# bms_board.net
KiCad netlist of a schematic drawn in EAGLE
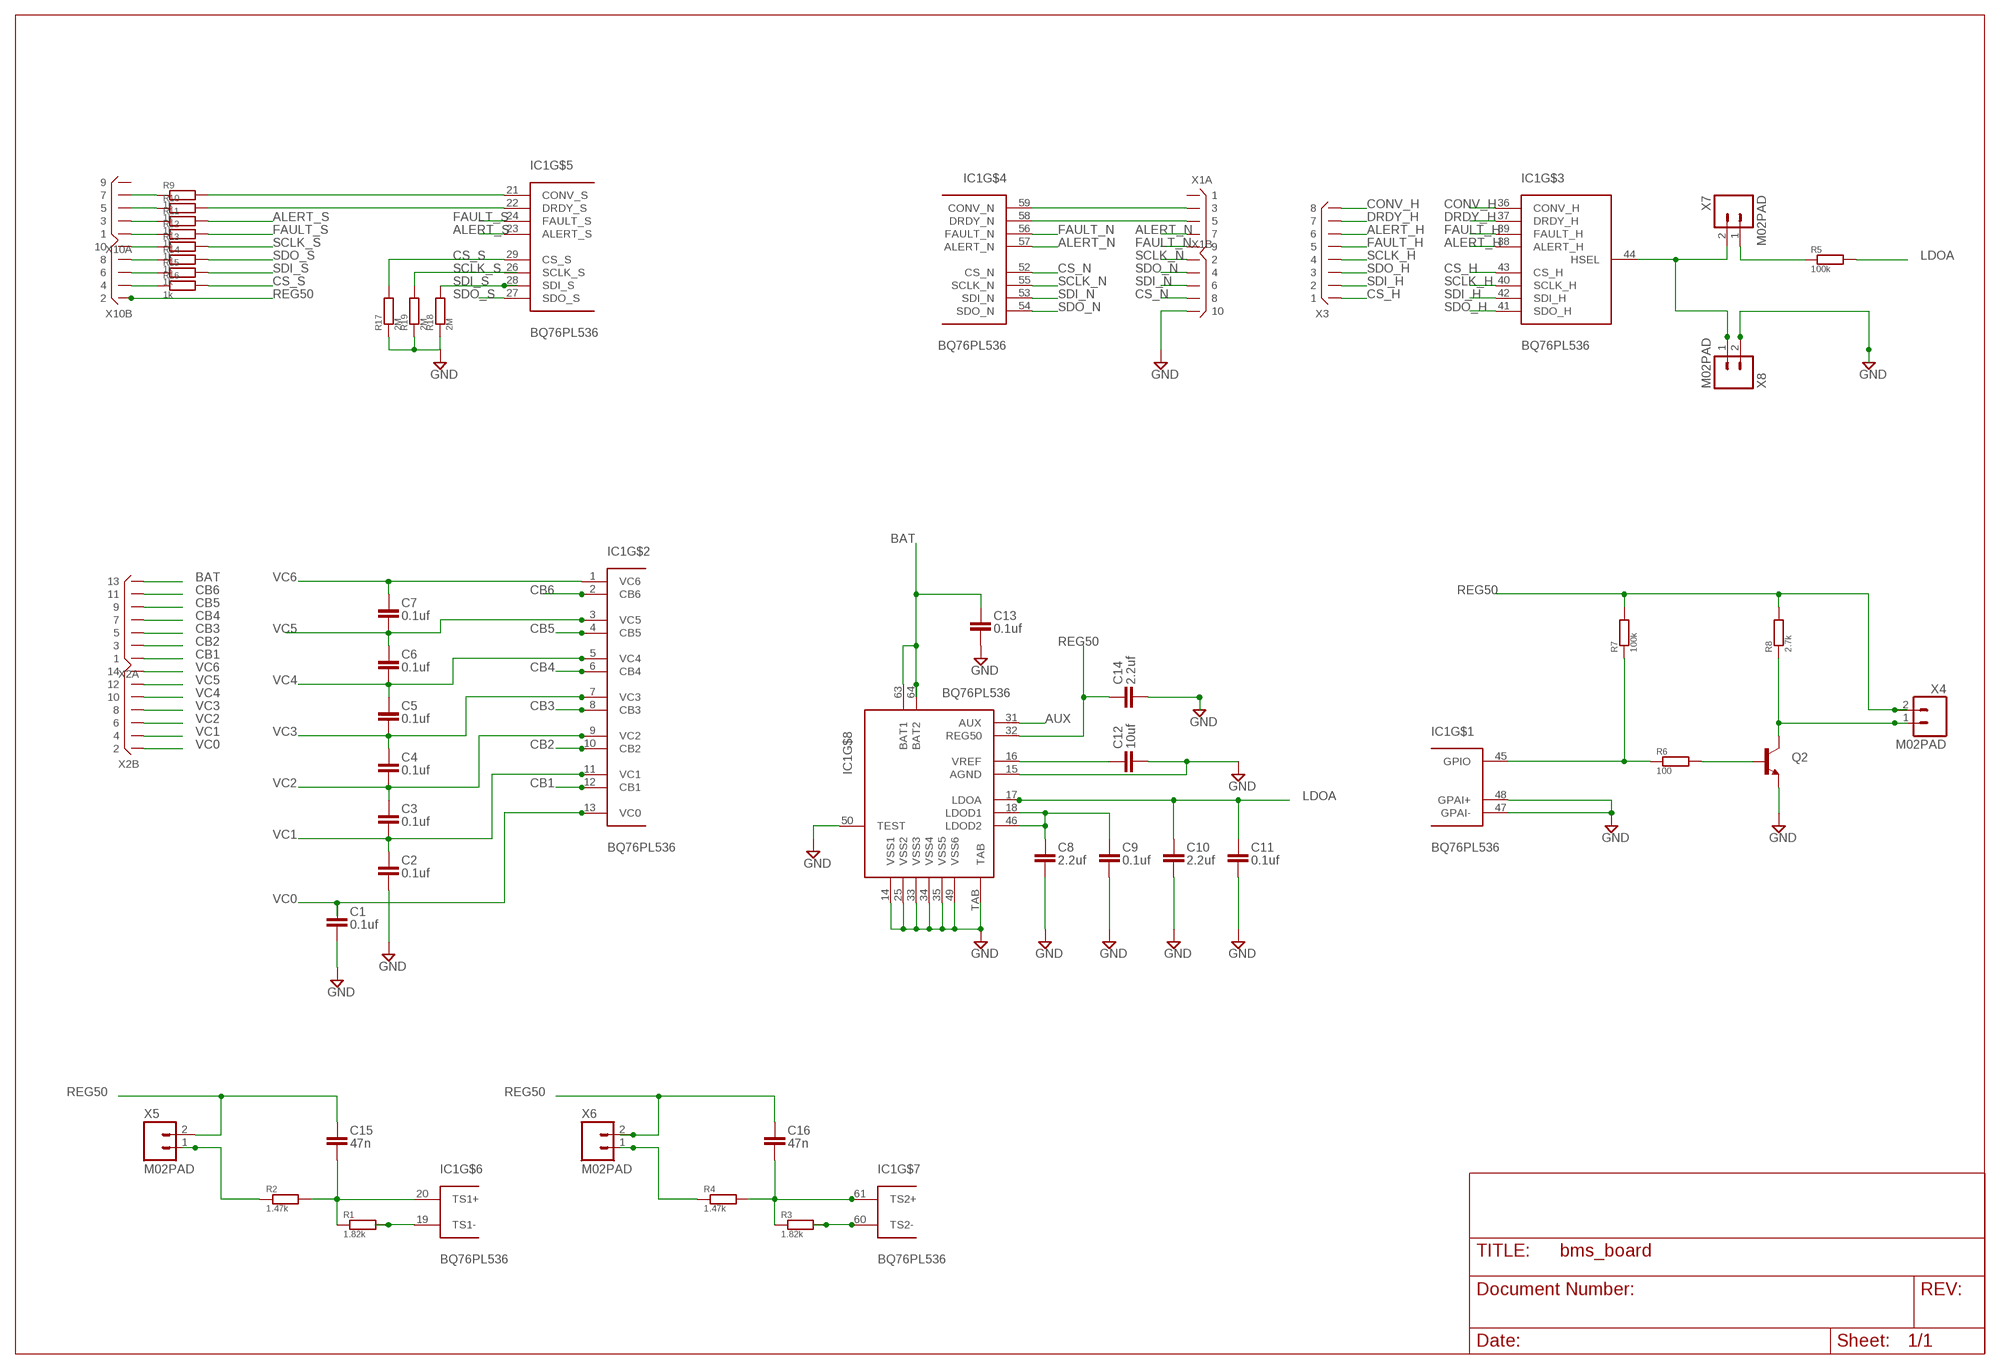
[diagram p0: schematic, sheet 1]

(export (version "E")
  (design (tool "Eeschema 10.0.6"))
  (components
    (comp (ref "C1")
      (value "0.1uf")
      (footprint "eagle-import:C0805")
      (libsource (lib "eagle-import") (part "CSTD"))
    )
    (comp (ref "C2")
      (value "0.1uf")
      (footprint "eagle-import:C0805")
      (libsource (lib "eagle-import") (part "CSTD"))
    )
    (comp (ref "C3")
      (value "0.1uf")
      (footprint "eagle-import:C0805")
      (libsource (lib "eagle-import") (part "CSTD"))
    )
    (comp (ref "C4")
      (value "0.1uf")
      (footprint "eagle-import:C0805")
      (libsource (lib "eagle-import") (part "CSTD"))
    )
    (comp (ref "C5")
      (value "0.1uf")
      (footprint "eagle-import:C0805")
      (libsource (lib "eagle-import") (part "CSTD"))
    )
    (comp (ref "C6")
      (value "0.1uf")
      (footprint "eagle-import:C0805")
      (libsource (lib "eagle-import") (part "CSTD"))
    )
    (comp (ref "C7")
      (value "0.1uf")
      (footprint "eagle-import:C0805")
      (libsource (lib "eagle-import") (part "CSTD"))
    )
    (comp (ref "C8")
      (value "2.2uf")
      (footprint "eagle-import:C0805")
      (libsource (lib "eagle-import") (part "CSTD"))
    )
    (comp (ref "C9")
      (value "0.1uf")
      (footprint "eagle-import:C0805")
      (libsource (lib "eagle-import") (part "CSTD"))
    )
    (comp (ref "C10")
      (value "2.2uf")
      (footprint "eagle-import:C0805")
      (libsource (lib "eagle-import") (part "CSTD"))
    )
    (comp (ref "C11")
      (value "0.1uf")
      (footprint "eagle-import:C0805")
      (libsource (lib "eagle-import") (part "CSTD"))
    )
    (comp (ref "C12")
      (value "10uf")
      (footprint "eagle-import:C0805")
      (libsource (lib "eagle-import") (part "CSTD"))
    )
    (comp (ref "C13")
      (value "0.1uf")
      (footprint "eagle-import:C0805")
      (libsource (lib "eagle-import") (part "CSTD"))
    )
    (comp (ref "C14")
      (value "2.2uf")
      (footprint "eagle-import:C0805")
      (libsource (lib "eagle-import") (part "CSTD"))
    )
    (comp (ref "C15")
      (value "47n")
      (footprint "eagle-import:C0805")
      (libsource (lib "eagle-import") (part "CSTD"))
    )
    (comp (ref "C16")
      (value "47n")
      (footprint "eagle-import:C0805")
      (libsource (lib "eagle-import") (part "CSTD"))
    )
    (comp (ref "IC1")
      (value "BQ76PL536")
      (footprint "eagle-import:LQFP-64")
      (libsource (lib "eagle-import") (part "BQ76PL536"))
    )
    (comp (ref "Q2")
      (value "TRANSISTOR_NPNSOT23")
      (footprint "eagle-import:SOT23")
      (libsource (lib "eagle-import") (part "TRANSISTOR_NPNSOT23"))
    )
    (comp (ref "R1")
      (value "1.82k")
      (footprint "eagle-import:R0805")
      (libsource (lib "eagle-import") (part "R"))
    )
    (comp (ref "R2")
      (value "1.47k")
      (footprint "eagle-import:R0805")
      (libsource (lib "eagle-import") (part "R"))
    )
    (comp (ref "R3")
      (value "1.82k")
      (footprint "eagle-import:R0805")
      (libsource (lib "eagle-import") (part "R"))
    )
    (comp (ref "R4")
      (value "1.47k")
      (footprint "eagle-import:R0805")
      (libsource (lib "eagle-import") (part "R"))
    )
    (comp (ref "R5")
      (value "100k")
      (footprint "eagle-import:R0805")
      (libsource (lib "eagle-import") (part "R"))
    )
    (comp (ref "R6")
      (value "100")
      (footprint "eagle-import:R0805")
      (libsource (lib "eagle-import") (part "R"))
    )
    (comp (ref "R7")
      (value "100k")
      (footprint "eagle-import:R0805")
      (libsource (lib "eagle-import") (part "R"))
    )
    (comp (ref "R8")
      (value "2.7k")
      (footprint "eagle-import:R0805")
      (libsource (lib "eagle-import") (part "R"))
    )
    (comp (ref "R9")
      (value "1k")
      (footprint "eagle-import:R0805")
      (libsource (lib "eagle-import") (part "R"))
    )
    (comp (ref "R10")
      (value "1k")
      (footprint "eagle-import:R0805")
      (libsource (lib "eagle-import") (part "R"))
    )
    (comp (ref "R11")
      (value "1k")
      (footprint "eagle-import:R0805")
      (libsource (lib "eagle-import") (part "R"))
    )
    (comp (ref "R12")
      (value "1k")
      (footprint "eagle-import:R0805")
      (libsource (lib "eagle-import") (part "R"))
    )
    (comp (ref "R13")
      (value "1k")
      (footprint "eagle-import:R0805")
      (libsource (lib "eagle-import") (part "R"))
    )
    (comp (ref "R14")
      (value "1k")
      (footprint "eagle-import:R0805")
      (libsource (lib "eagle-import") (part "R"))
    )
    (comp (ref "R15")
      (value "1k")
      (footprint "eagle-import:R0805")
      (libsource (lib "eagle-import") (part "R"))
    )
    (comp (ref "R16")
      (value "1k")
      (footprint "eagle-import:R0805")
      (libsource (lib "eagle-import") (part "R"))
    )
    (comp (ref "R17")
      (value "2M")
      (footprint "eagle-import:R0805")
      (libsource (lib "eagle-import") (part "R"))
    )
    (comp (ref "R18")
      (value "2M")
      (footprint "eagle-import:R0805")
      (libsource (lib "eagle-import") (part "R"))
    )
    (comp (ref "R19")
      (value "2M")
      (footprint "eagle-import:R0805")
      (libsource (lib "eagle-import") (part "R"))
    )
    (comp (ref "X1")
      (value "X05X2ICR")
      (footprint "eagle-import:X10ICR")
      (libsource (lib "eagle-import") (part "X05X2ICR"))
    )
    (comp (ref "X2")
      (value "X07X2IR")
      (footprint "eagle-import:X14R-IDC")
      (libsource (lib "eagle-import") (part "X07X2IR"))
    )
    (comp (ref "X3")
      (value "X08R")
      (footprint "eagle-import:X08R-SIL")
      (libsource (lib "eagle-import") (part "X08R"))
    )
    (comp (ref "X4")
      (value "M02PAD")
      (footprint "eagle-import:1X02")
      (libsource (lib "eagle-import") (part "M02PAD"))
    )
    (comp (ref "X5")
      (value "M02PAD")
      (footprint "eagle-import:1X02")
      (libsource (lib "eagle-import") (part "M02PAD"))
    )
    (comp (ref "X6")
      (value "M02PAD")
      (footprint "eagle-import:1X02")
      (libsource (lib "eagle-import") (part "M02PAD"))
    )
    (comp (ref "X7")
      (value "M02PAD")
      (footprint "eagle-import:1X02")
      (libsource (lib "eagle-import") (part "M02PAD"))
    )
    (comp (ref "X8")
      (value "M02PAD")
      (footprint "eagle-import:1X02")
      (libsource (lib "eagle-import") (part "M02PAD"))
    )
    (comp (ref "X10")
      (value "X05X2ICR")
      (footprint "eagle-import:X10ICR")
      (libsource (lib "eagle-import") (part "X05X2ICR"))
    )
  )
  (nets
    (net (code "1") (name "/ALERT_H") (class "Default")
      (node (ref "IC1") (pin "38") (pinfunction "ALERT_H_38") (pintype "bidirectional"))
      (node (ref "X3") (pin "6") (pinfunction "6_6") (pintype "bidirectional"))
    )
    (net (code "2") (name "/ALERT_N") (class "Default")
      (node (ref "IC1") (pin "57") (pinfunction "ALERT_N_57") (pintype "bidirectional"))
      (node (ref "X1") (pin "7") (pinfunction "7_7") (pintype "bidirectional"))
    )
    (net (code "3") (name "/ALERT_S") (class "Default")
      (node (ref "IC1") (pin "23") (pinfunction "ALERT_S_23") (pintype "bidirectional"))
      (node (ref "R11") (pin "2") (pinfunction "2_2") (pintype "passive"))
    )
    (net (code "4") (name "/AUX") (class "Default")
      (node (ref "IC1") (pin "31") (pinfunction "AUX_31") (pintype "bidirectional"))
    )
    (net (code "5") (name "/BAT") (class "Default")
      (node (ref "C13") (pin "2") (pinfunction "2_2") (pintype "passive"))
      (node (ref "IC1") (pin "63") (pinfunction "BAT1_63") (pintype "bidirectional"))
      (node (ref "IC1") (pin "64") (pinfunction "BAT2_64") (pintype "bidirectional"))
      (node (ref "X2") (pin "13") (pinfunction "13_13") (pintype "bidirectional"))
    )
    (net (code "6") (name "/CB1") (class "Default")
      (node (ref "IC1") (pin "12") (pinfunction "CB1_12") (pintype "bidirectional"))
      (node (ref "X2") (pin "1") (pinfunction "1_1") (pintype "bidirectional"))
    )
    (net (code "7") (name "/CB2") (class "Default")
      (node (ref "IC1") (pin "10") (pinfunction "CB2_10") (pintype "bidirectional"))
      (node (ref "X2") (pin "3") (pinfunction "3_3") (pintype "bidirectional"))
    )
    (net (code "8") (name "/CB3") (class "Default")
      (node (ref "IC1") (pin "8") (pinfunction "CB3_8") (pintype "bidirectional"))
      (node (ref "X2") (pin "5") (pinfunction "5_5") (pintype "bidirectional"))
    )
    (net (code "9") (name "/CB4") (class "Default")
      (node (ref "IC1") (pin "6") (pinfunction "CB4_6") (pintype "bidirectional"))
      (node (ref "X2") (pin "7") (pinfunction "7_7") (pintype "bidirectional"))
    )
    (net (code "10") (name "/CB5") (class "Default")
      (node (ref "IC1") (pin "4") (pinfunction "CB5_4") (pintype "bidirectional"))
      (node (ref "X2") (pin "9") (pinfunction "9_9") (pintype "bidirectional"))
    )
    (net (code "11") (name "/CB6") (class "Default")
      (node (ref "IC1") (pin "2") (pinfunction "CB6_2") (pintype "bidirectional"))
      (node (ref "X2") (pin "11") (pinfunction "11_11") (pintype "bidirectional"))
    )
    (net (code "12") (name "/CONV_H") (class "Default")
      (node (ref "IC1") (pin "36") (pinfunction "CONV_H_36") (pintype "bidirectional"))
      (node (ref "X3") (pin "8") (pinfunction "8_8") (pintype "bidirectional"))
    )
    (net (code "13") (name "/CS_H") (class "Default")
      (node (ref "IC1") (pin "43") (pinfunction "CS_H_43") (pintype "bidirectional"))
      (node (ref "X3") (pin "1") (pinfunction "1_1") (pintype "bidirectional"))
    )
    (net (code "14") (name "/CS_N") (class "Default")
      (node (ref "IC1") (pin "52") (pinfunction "CS_N_52") (pintype "bidirectional"))
      (node (ref "X1") (pin "8") (pinfunction "8_8") (pintype "bidirectional"))
    )
    (net (code "15") (name "/CS_S") (class "Default")
      (node (ref "IC1") (pin "29") (pinfunction "CS_S_29") (pintype "bidirectional"))
      (node (ref "R16") (pin "2") (pinfunction "2_2") (pintype "passive"))
      (node (ref "R17") (pin "2") (pinfunction "2_2") (pintype "passive"))
    )
    (net (code "16") (name "/DRDY_H") (class "Default")
      (node (ref "IC1") (pin "37") (pinfunction "DRDY_H_37") (pintype "bidirectional"))
      (node (ref "X3") (pin "7") (pinfunction "7_7") (pintype "bidirectional"))
    )
    (net (code "17") (name "/FAULT_H") (class "Default")
      (node (ref "IC1") (pin "39") (pinfunction "FAULT_H_39") (pintype "bidirectional"))
      (node (ref "X3") (pin "5") (pinfunction "5_5") (pintype "bidirectional"))
    )
    (net (code "18") (name "/FAULT_N") (class "Default")
      (node (ref "IC1") (pin "56") (pinfunction "FAULT_N_56") (pintype "bidirectional"))
      (node (ref "X1") (pin "9") (pinfunction "9_9") (pintype "bidirectional"))
    )
    (net (code "19") (name "/FAULT_S") (class "Default")
      (node (ref "IC1") (pin "24") (pinfunction "FAULT_S_24") (pintype "bidirectional"))
      (node (ref "R12") (pin "2") (pinfunction "2_2") (pintype "passive"))
    )
    (net (code "20") (name "/LDOA") (class "Default")
      (node (ref "C10") (pin "2") (pinfunction "2_2") (pintype "passive"))
      (node (ref "C11") (pin "2") (pinfunction "2_2") (pintype "passive"))
      (node (ref "IC1") (pin "17") (pinfunction "LDOA_17") (pintype "bidirectional"))
      (node (ref "R5") (pin "2") (pinfunction "2_2") (pintype "passive"))
    )
    (net (code "21") (name "/REG50") (class "Default")
      (node (ref "C14") (pin "2") (pinfunction "2_2") (pintype "passive"))
      (node (ref "C15") (pin "2") (pinfunction "2_2") (pintype "passive"))
      (node (ref "C16") (pin "2") (pinfunction "2_2") (pintype "passive"))
      (node (ref "IC1") (pin "32") (pinfunction "REG50_32") (pintype "bidirectional"))
      (node (ref "R7") (pin "2") (pinfunction "2_2") (pintype "passive"))
      (node (ref "R8") (pin "2") (pinfunction "2_2") (pintype "passive"))
      (node (ref "X10") (pin "2") (pinfunction "2_2") (pintype "bidirectional"))
      (node (ref "X4") (pin "2") (pinfunction "2_2") (pintype "passive"))
      (node (ref "X5") (pin "2") (pinfunction "2_2") (pintype "passive"))
      (node (ref "X6") (pin "2") (pinfunction "2_2") (pintype "passive"))
    )
    (net (code "22") (name "/SCLK_H") (class "Default")
      (node (ref "IC1") (pin "40") (pinfunction "SCLK_H_40") (pintype "bidirectional"))
      (node (ref "X3") (pin "4") (pinfunction "4_4") (pintype "bidirectional"))
    )
    (net (code "23") (name "/SCLK_N") (class "Default")
      (node (ref "IC1") (pin "55") (pinfunction "SCLK_N_55") (pintype "bidirectional"))
      (node (ref "X1") (pin "2") (pinfunction "2_2") (pintype "bidirectional"))
    )
    (net (code "24") (name "/SCLK_S") (class "Default")
      (node (ref "IC1") (pin "26") (pinfunction "SCLK_S_26") (pintype "bidirectional"))
      (node (ref "R13") (pin "2") (pinfunction "2_2") (pintype "passive"))
      (node (ref "R19") (pin "2") (pinfunction "2_2") (pintype "passive"))
    )
    (net (code "25") (name "/SDI_H") (class "Default")
      (node (ref "IC1") (pin "42") (pinfunction "SDI_H_42") (pintype "bidirectional"))
      (node (ref "X3") (pin "2") (pinfunction "2_2") (pintype "bidirectional"))
    )
    (net (code "26") (name "/SDI_N") (class "Default")
      (node (ref "IC1") (pin "53") (pinfunction "SDI_N_53") (pintype "bidirectional"))
      (node (ref "X1") (pin "6") (pinfunction "6_6") (pintype "bidirectional"))
    )
    (net (code "27") (name "/SDI_S") (class "Default")
      (node (ref "IC1") (pin "28") (pinfunction "SDI_S_28") (pintype "bidirectional"))
      (node (ref "R15") (pin "2") (pinfunction "2_2") (pintype "passive"))
      (node (ref "R18") (pin "2") (pinfunction "2_2") (pintype "passive"))
    )
    (net (code "28") (name "/SDO_H") (class "Default")
      (node (ref "IC1") (pin "41") (pinfunction "SDO_H_41") (pintype "bidirectional"))
      (node (ref "X3") (pin "3") (pinfunction "3_3") (pintype "bidirectional"))
    )
    (net (code "29") (name "/SDO_N") (class "Default")
      (node (ref "IC1") (pin "54") (pinfunction "SDO_N_54") (pintype "bidirectional"))
      (node (ref "X1") (pin "4") (pinfunction "4_4") (pintype "bidirectional"))
    )
    (net (code "30") (name "/SDO_S") (class "Default")
      (node (ref "IC1") (pin "27") (pinfunction "SDO_S_27") (pintype "bidirectional"))
      (node (ref "R14") (pin "2") (pinfunction "2_2") (pintype "passive"))
    )
    (net (code "31") (name "/VC0") (class "Default")
      (node (ref "C1") (pin "2") (pinfunction "2_2") (pintype "passive"))
      (node (ref "IC1") (pin "13") (pinfunction "VC0_13") (pintype "bidirectional"))
      (node (ref "X2") (pin "2") (pinfunction "2_2") (pintype "bidirectional"))
    )
    (net (code "32") (name "/VC1") (class "Default")
      (node (ref "C2") (pin "2") (pinfunction "2_2") (pintype "passive"))
      (node (ref "C3") (pin "1") (pinfunction "1_1") (pintype "passive"))
      (node (ref "IC1") (pin "11") (pinfunction "VC1_11") (pintype "bidirectional"))
      (node (ref "X2") (pin "4") (pinfunction "4_4") (pintype "bidirectional"))
    )
    (net (code "33") (name "/VC2") (class "Default")
      (node (ref "C3") (pin "2") (pinfunction "2_2") (pintype "passive"))
      (node (ref "C4") (pin "1") (pinfunction "1_1") (pintype "passive"))
      (node (ref "IC1") (pin "9") (pinfunction "VC2_9") (pintype "bidirectional"))
      (node (ref "X2") (pin "6") (pinfunction "6_6") (pintype "bidirectional"))
    )
    (net (code "34") (name "/VC3") (class "Default")
      (node (ref "C4") (pin "2") (pinfunction "2_2") (pintype "passive"))
      (node (ref "C5") (pin "1") (pinfunction "1_1") (pintype "passive"))
      (node (ref "IC1") (pin "7") (pinfunction "VC3_7") (pintype "bidirectional"))
      (node (ref "X2") (pin "8") (pinfunction "8_8") (pintype "bidirectional"))
    )
    (net (code "35") (name "/VC4") (class "Default")
      (node (ref "C5") (pin "2") (pinfunction "2_2") (pintype "passive"))
      (node (ref "C6") (pin "1") (pinfunction "1_1") (pintype "passive"))
      (node (ref "IC1") (pin "5") (pinfunction "VC4_5") (pintype "bidirectional"))
      (node (ref "X2") (pin "10") (pinfunction "10_10") (pintype "bidirectional"))
    )
    (net (code "36") (name "/VC5") (class "Default")
      (node (ref "C6") (pin "2") (pinfunction "2_2") (pintype "passive"))
      (node (ref "C7") (pin "1") (pinfunction "1_1") (pintype "passive"))
      (node (ref "IC1") (pin "3") (pinfunction "VC5_3") (pintype "bidirectional"))
      (node (ref "X2") (pin "12") (pinfunction "12_12") (pintype "bidirectional"))
    )
    (net (code "37") (name "/VC6") (class "Default")
      (node (ref "C7") (pin "2") (pinfunction "2_2") (pintype "passive"))
      (node (ref "IC1") (pin "1") (pinfunction "VC6_1") (pintype "bidirectional"))
      (node (ref "X2") (pin "14") (pinfunction "14_14") (pintype "bidirectional"))
    )
    (net (code "38") (name "GND") (class "Default")
      (node (ref "C1") (pin "1") (pinfunction "1_1") (pintype "passive"))
      (node (ref "C10") (pin "1") (pinfunction "1_1") (pintype "passive"))
      (node (ref "C11") (pin "1") (pinfunction "1_1") (pintype "passive"))
      (node (ref "C12") (pin "1") (pinfunction "1_1") (pintype "passive"))
      (node (ref "C13") (pin "1") (pinfunction "1_1") (pintype "passive"))
      (node (ref "C14") (pin "1") (pinfunction "1_1") (pintype "passive"))
      (node (ref "C2") (pin "1") (pinfunction "1_1") (pintype "passive"))
      (node (ref "C8") (pin "1") (pinfunction "1_1") (pintype "passive"))
      (node (ref "C9") (pin "1") (pinfunction "1_1") (pintype "passive"))
      (node (ref "IC1") (pin "14") (pinfunction "VSS1_14") (pintype "bidirectional"))
      (node (ref "IC1") (pin "15") (pinfunction "AGND_15") (pintype "bidirectional"))
      (node (ref "IC1") (pin "25") (pinfunction "VSS2_25") (pintype "bidirectional"))
      (node (ref "IC1") (pin "33") (pinfunction "VSS3_33") (pintype "bidirectional"))
      (node (ref "IC1") (pin "34") (pinfunction "VSS4_34") (pintype "bidirectional"))
      (node (ref "IC1") (pin "35") (pinfunction "VSS5_35") (pintype "bidirectional"))
      (node (ref "IC1") (pin "47") (pinfunction "GPAI-_47") (pintype "bidirectional"))
      (node (ref "IC1") (pin "48") (pinfunction "GPAI+_48") (pintype "bidirectional"))
      (node (ref "IC1") (pin "49") (pinfunction "VSS6_49") (pintype "bidirectional"))
      (node (ref "IC1") (pin "50") (pinfunction "TEST_50") (pintype "bidirectional"))
      (node (ref "IC1") (pin "TAB") (pinfunction "TAB_TAB") (pintype "bidirectional"))
      (node (ref "Q2") (pin "2") (pinfunction "E_2") (pintype "passive"))
      (node (ref "R17") (pin "1") (pinfunction "1_1") (pintype "passive"))
      (node (ref "R18") (pin "1") (pinfunction "1_1") (pintype "passive"))
      (node (ref "R19") (pin "1") (pinfunction "1_1") (pintype "passive"))
      (node (ref "X1") (pin "10") (pinfunction "10_10") (pintype "bidirectional"))
      (node (ref "X8") (pin "2") (pinfunction "2_2") (pintype "passive"))
    )
    (net (code "39") (name "Net-(IC1A-GPIO)") (class "Default")
      (node (ref "IC1") (pin "45") (pinfunction "GPIO_45") (pintype "bidirectional"))
      (node (ref "R6") (pin "1") (pinfunction "1_1") (pintype "passive"))
      (node (ref "R7") (pin "1") (pinfunction "1_1") (pintype "passive"))
    )
    (net (code "40") (name "Net-(IC1C-HSEL)") (class "Default")
      (node (ref "IC1") (pin "44") (pinfunction "HSEL_44") (pintype "bidirectional"))
      (node (ref "X7") (pin "2") (pinfunction "2_2") (pintype "passive"))
      (node (ref "X8") (pin "1") (pinfunction "1_1") (pintype "passive"))
    )
    (net (code "41") (name "Net-(IC1D-CONV_N)") (class "Default")
      (node (ref "IC1") (pin "59") (pinfunction "CONV_N_59") (pintype "bidirectional"))
      (node (ref "X1") (pin "3") (pinfunction "3_3") (pintype "bidirectional"))
    )
    (net (code "42") (name "Net-(IC1D-DRDY_N)") (class "Default")
      (node (ref "IC1") (pin "58") (pinfunction "DRDY_N_58") (pintype "bidirectional"))
      (node (ref "X1") (pin "5") (pinfunction "5_5") (pintype "bidirectional"))
    )
    (net (code "43") (name "Net-(IC1E-CONV_S)") (class "Default")
      (node (ref "IC1") (pin "21") (pinfunction "CONV_S_21") (pintype "bidirectional"))
      (node (ref "R9") (pin "2") (pinfunction "2_2") (pintype "passive"))
    )
    (net (code "44") (name "Net-(IC1E-DRDY_S)") (class "Default")
      (node (ref "IC1") (pin "22") (pinfunction "DRDY_S_22") (pintype "bidirectional"))
      (node (ref "R10") (pin "2") (pinfunction "2_2") (pintype "passive"))
    )
    (net (code "45") (name "Net-(IC1F-TS1+)") (class "Default")
      (node (ref "C15") (pin "1") (pinfunction "1_1") (pintype "passive"))
      (node (ref "IC1") (pin "20") (pinfunction "TS1+_20") (pintype "bidirectional"))
      (node (ref "R1") (pin "1") (pinfunction "1_1") (pintype "passive"))
      (node (ref "R2") (pin "2") (pinfunction "2_2") (pintype "passive"))
    )
    (net (code "46") (name "Net-(IC1F-TS1-)") (class "Default")
      (node (ref "IC1") (pin "19") (pinfunction "TS1-_19") (pintype "bidirectional"))
      (node (ref "R1") (pin "2") (pinfunction "2_2") (pintype "passive"))
    )
    (net (code "47") (name "Net-(IC1G-TS2+)") (class "Default")
      (node (ref "C16") (pin "1") (pinfunction "1_1") (pintype "passive"))
      (node (ref "IC1") (pin "61") (pinfunction "TS2+_61") (pintype "bidirectional"))
      (node (ref "R3") (pin "1") (pinfunction "1_1") (pintype "passive"))
      (node (ref "R4") (pin "2") (pinfunction "2_2") (pintype "passive"))
    )
    (net (code "48") (name "Net-(IC1G-TS2-)") (class "Default")
      (node (ref "IC1") (pin "60") (pinfunction "TS2-_60") (pintype "bidirectional"))
      (node (ref "R3") (pin "2") (pinfunction "2_2") (pintype "passive"))
    )
    (net (code "49") (name "Net-(IC1H-LDOD1)") (class "Default")
      (node (ref "C8") (pin "2") (pinfunction "2_2") (pintype "passive"))
      (node (ref "C9") (pin "2") (pinfunction "2_2") (pintype "passive"))
      (node (ref "IC1") (pin "18") (pinfunction "LDOD1_18") (pintype "bidirectional"))
      (node (ref "IC1") (pin "46") (pinfunction "LDOD2_46") (pintype "bidirectional"))
    )
    (net (code "50") (name "Net-(IC1H-VREF)") (class "Default")
      (node (ref "C12") (pin "2") (pinfunction "2_2") (pintype "passive"))
      (node (ref "IC1") (pin "16") (pinfunction "VREF_16") (pintype "bidirectional"))
    )
    (net (code "51") (name "Net-(Q2-B)") (class "Default")
      (node (ref "Q2") (pin "1") (pinfunction "B_1") (pintype "passive"))
      (node (ref "R6") (pin "2") (pinfunction "2_2") (pintype "passive"))
    )
    (net (code "52") (name "Net-(Q2-C)") (class "Default")
      (node (ref "Q2") (pin "3") (pinfunction "C_3") (pintype "passive"))
      (node (ref "R8") (pin "1") (pinfunction "1_1") (pintype "passive"))
      (node (ref "X4") (pin "1") (pinfunction "1_1") (pintype "passive"))
    )
    (net (code "53") (name "Net-(R2-Pad1)") (class "Default")
      (node (ref "R2") (pin "1") (pinfunction "1_1") (pintype "passive"))
      (node (ref "X5") (pin "1") (pinfunction "1_1") (pintype "passive"))
    )
    (net (code "54") (name "Net-(R4-Pad1)") (class "Default")
      (node (ref "R4") (pin "1") (pinfunction "1_1") (pintype "passive"))
      (node (ref "X6") (pin "1") (pinfunction "1_1") (pintype "passive"))
    )
    (net (code "55") (name "Net-(R5-Pad1)") (class "Default")
      (node (ref "R5") (pin "1") (pinfunction "1_1") (pintype "passive"))
      (node (ref "X7") (pin "1") (pinfunction "1_1") (pintype "passive"))
    )
    (net (code "56") (name "Net-(R9-Pad1)") (class "Default")
      (node (ref "R9") (pin "1") (pinfunction "1_1") (pintype "passive"))
      (node (ref "X10") (pin "7") (pinfunction "7_7") (pintype "bidirectional"))
    )
    (net (code "57") (name "Net-(R10-Pad1)") (class "Default")
      (node (ref "R10") (pin "1") (pinfunction "1_1") (pintype "passive"))
      (node (ref "X10") (pin "5") (pinfunction "5_5") (pintype "bidirectional"))
    )
    (net (code "58") (name "Net-(R11-Pad1)") (class "Default")
      (node (ref "R11") (pin "1") (pinfunction "1_1") (pintype "passive"))
      (node (ref "X10") (pin "3") (pinfunction "3_3") (pintype "bidirectional"))
    )
    (net (code "59") (name "Net-(R12-Pad1)") (class "Default")
      (node (ref "R12") (pin "1") (pinfunction "1_1") (pintype "passive"))
      (node (ref "X10") (pin "1") (pinfunction "1_1") (pintype "bidirectional"))
    )
    (net (code "60") (name "Net-(R13-Pad1)") (class "Default")
      (node (ref "R13") (pin "1") (pinfunction "1_1") (pintype "passive"))
      (node (ref "X10") (pin "10") (pinfunction "10_10") (pintype "bidirectional"))
    )
    (net (code "61") (name "Net-(R14-Pad1)") (class "Default")
      (node (ref "R14") (pin "1") (pinfunction "1_1") (pintype "passive"))
      (node (ref "X10") (pin "8") (pinfunction "8_8") (pintype "bidirectional"))
    )
    (net (code "62") (name "Net-(R15-Pad1)") (class "Default")
      (node (ref "R15") (pin "1") (pinfunction "1_1") (pintype "passive"))
      (node (ref "X10") (pin "6") (pinfunction "6_6") (pintype "bidirectional"))
    )
    (net (code "63") (name "Net-(R16-Pad1)") (class "Default")
      (node (ref "R16") (pin "1") (pinfunction "1_1") (pintype "passive"))
      (node (ref "X10") (pin "4") (pinfunction "4_4") (pintype "bidirectional"))
    )
    (net (code "64") (name "unconnected-(X1-Pad1)") (class "Default")
      (node (ref "X1") (pin "1") (pinfunction "1_1") (pintype "bidirectional"))
    )
    (net (code "65") (name "unconnected-(X10-Pad9)") (class "Default")
      (node (ref "X10") (pin "9") (pinfunction "9_9") (pintype "bidirectional"))
    )
  )
)
